# PowerMonitor.net
KiCad netlist of a schematic drawn in Altium Designer
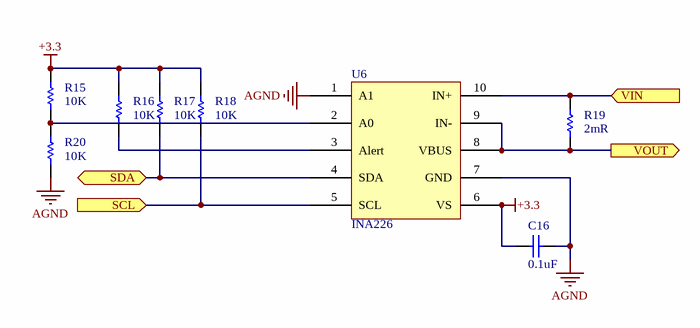
[diagram p0: PowerMonitor.SchDoc]

(export (version "E")
  (design (tool "Eeschema 10.0.6"))
  (components
    (comp (ref "C16")
      (value "0.1uF")
      (footprint "C 0603_L")
      (description "X5R 50V")
      (fields (field (name "Comment") "Cap") (field (name "PUBLISHER") "Altium Limited"))
      (libsource (lib "Miscellaneous Devices") (part "Cap"))
    )
    (comp (ref "R15")
      (value "10K")
      (footprint "R 0603_L")
      (description "Resistor")
      (fields (field (name "Comment") "Res1") (field (name "PUBLISHER") "Altium Limited"))
      (libsource (lib "Miscellaneous Devices") (part "Res1"))
    )
    (comp (ref "R16")
      (value "10K")
      (footprint "R 0603_L")
      (description "Resistor")
      (fields (field (name "Comment") "Res1") (field (name "PUBLISHER") "Altium Limited"))
      (libsource (lib "Miscellaneous Devices") (part "Res1"))
    )
    (comp (ref "R17")
      (value "10K")
      (footprint "R 0603_L")
      (description "Resistor")
      (fields (field (name "Comment") "Res1") (field (name "PUBLISHER") "Altium Limited"))
      (libsource (lib "Miscellaneous Devices") (part "Res1"))
    )
    (comp (ref "R18")
      (value "10K")
      (footprint "R 0603_L")
      (description "Resistor")
      (fields (field (name "Comment") "Res1") (field (name "PUBLISHER") "Altium Limited"))
      (libsource (lib "Miscellaneous Devices") (part "Res1"))
    )
    (comp (ref "R19")
      (value "2mR")
      (footprint "R 2512_L")
      (description "Resistor")
      (fields (field (name "Comment") "Res1") (field (name "PUBLISHER") "Altium Limited"))
      (libsource (lib "Miscellaneous Devices") (part "Res1"))
    )
    (comp (ref "R20")
      (value "10K")
      (footprint "R 0603_L")
      (description "Resistor")
      (fields (field (name "Comment") "Res1") (field (name "PUBLISHER") "Altium Limited"))
      (libsource (lib "Miscellaneous Devices") (part "Res1"))
    )
    (comp (ref "U6") (value "INA226") (footprint "MSOP10_N") (libsource (lib "TI芯片") (part "INA226")))
  )
  (nets
    (net (code "1") (name "+3.3") (class "Default")
      (node (ref "C16") (pin "1") (pinfunction "1_1") (pintype "passive"))
      (node (ref "R15") (pin "2") (pinfunction "2_2") (pintype "passive"))
      (node (ref "R16") (pin "2") (pinfunction "2_2") (pintype "passive"))
      (node (ref "R17") (pin "2") (pinfunction "2_2") (pintype "passive"))
      (node (ref "R18") (pin "2") (pinfunction "2_2") (pintype "passive"))
      (node (ref "U6") (pin "6") (pinfunction "VS_6") (pintype "passive"))
    )
    (net (code "2") (name "/SCL") (class "Default")
      (node (ref "R18") (pin "1") (pinfunction "1_1") (pintype "passive"))
      (node (ref "U6") (pin "5") (pinfunction "SCL_5") (pintype "passive"))
    )
    (net (code "3") (name "/SDA") (class "Default")
      (node (ref "R17") (pin "1") (pinfunction "1_1") (pintype "passive"))
      (node (ref "U6") (pin "4") (pinfunction "SDA_4") (pintype "passive"))
    )
    (net (code "4") (name "/VIN") (class "Default")
      (node (ref "R19") (pin "2") (pinfunction "2_2") (pintype "passive"))
      (node (ref "U6") (pin "10") (pinfunction "IN+_10") (pintype "passive"))
    )
    (net (code "5") (name "/VOUT") (class "Default")
      (node (ref "R19") (pin "1") (pinfunction "1_1") (pintype "passive"))
      (node (ref "U6") (pin "8") (pinfunction "VBUS_8") (pintype "passive"))
      (node (ref "U6") (pin "9") (pinfunction "IN-_9") (pintype "passive"))
    )
    (net (code "6") (name "AGND") (class "Default")
      (node (ref "C16") (pin "2") (pinfunction "2_2") (pintype "passive"))
      (node (ref "R20") (pin "1") (pinfunction "1_1") (pintype "passive"))
      (node (ref "U6") (pin "1") (pinfunction "A1_1") (pintype "passive"))
      (node (ref "U6") (pin "7") (pinfunction "GND_7") (pintype "passive"))
    )
    (net (code "7") (name "Net-(U6-A0)") (class "Default")
      (node (ref "R15") (pin "1") (pinfunction "1_1") (pintype "passive"))
      (node (ref "R20") (pin "2") (pinfunction "2_2") (pintype "passive"))
      (node (ref "U6") (pin "2") (pinfunction "A0_2") (pintype "passive"))
    )
    (net (code "8") (name "Net-(U6-Alert)") (class "Default")
      (node (ref "R16") (pin "1") (pinfunction "1_1") (pintype "passive"))
      (node (ref "U6") (pin "3") (pinfunction "Alert_3") (pintype "passive"))
    )
  )
)
